# EEM_Connectors.net
KiCad netlist of a schematic drawn in Altium Designer
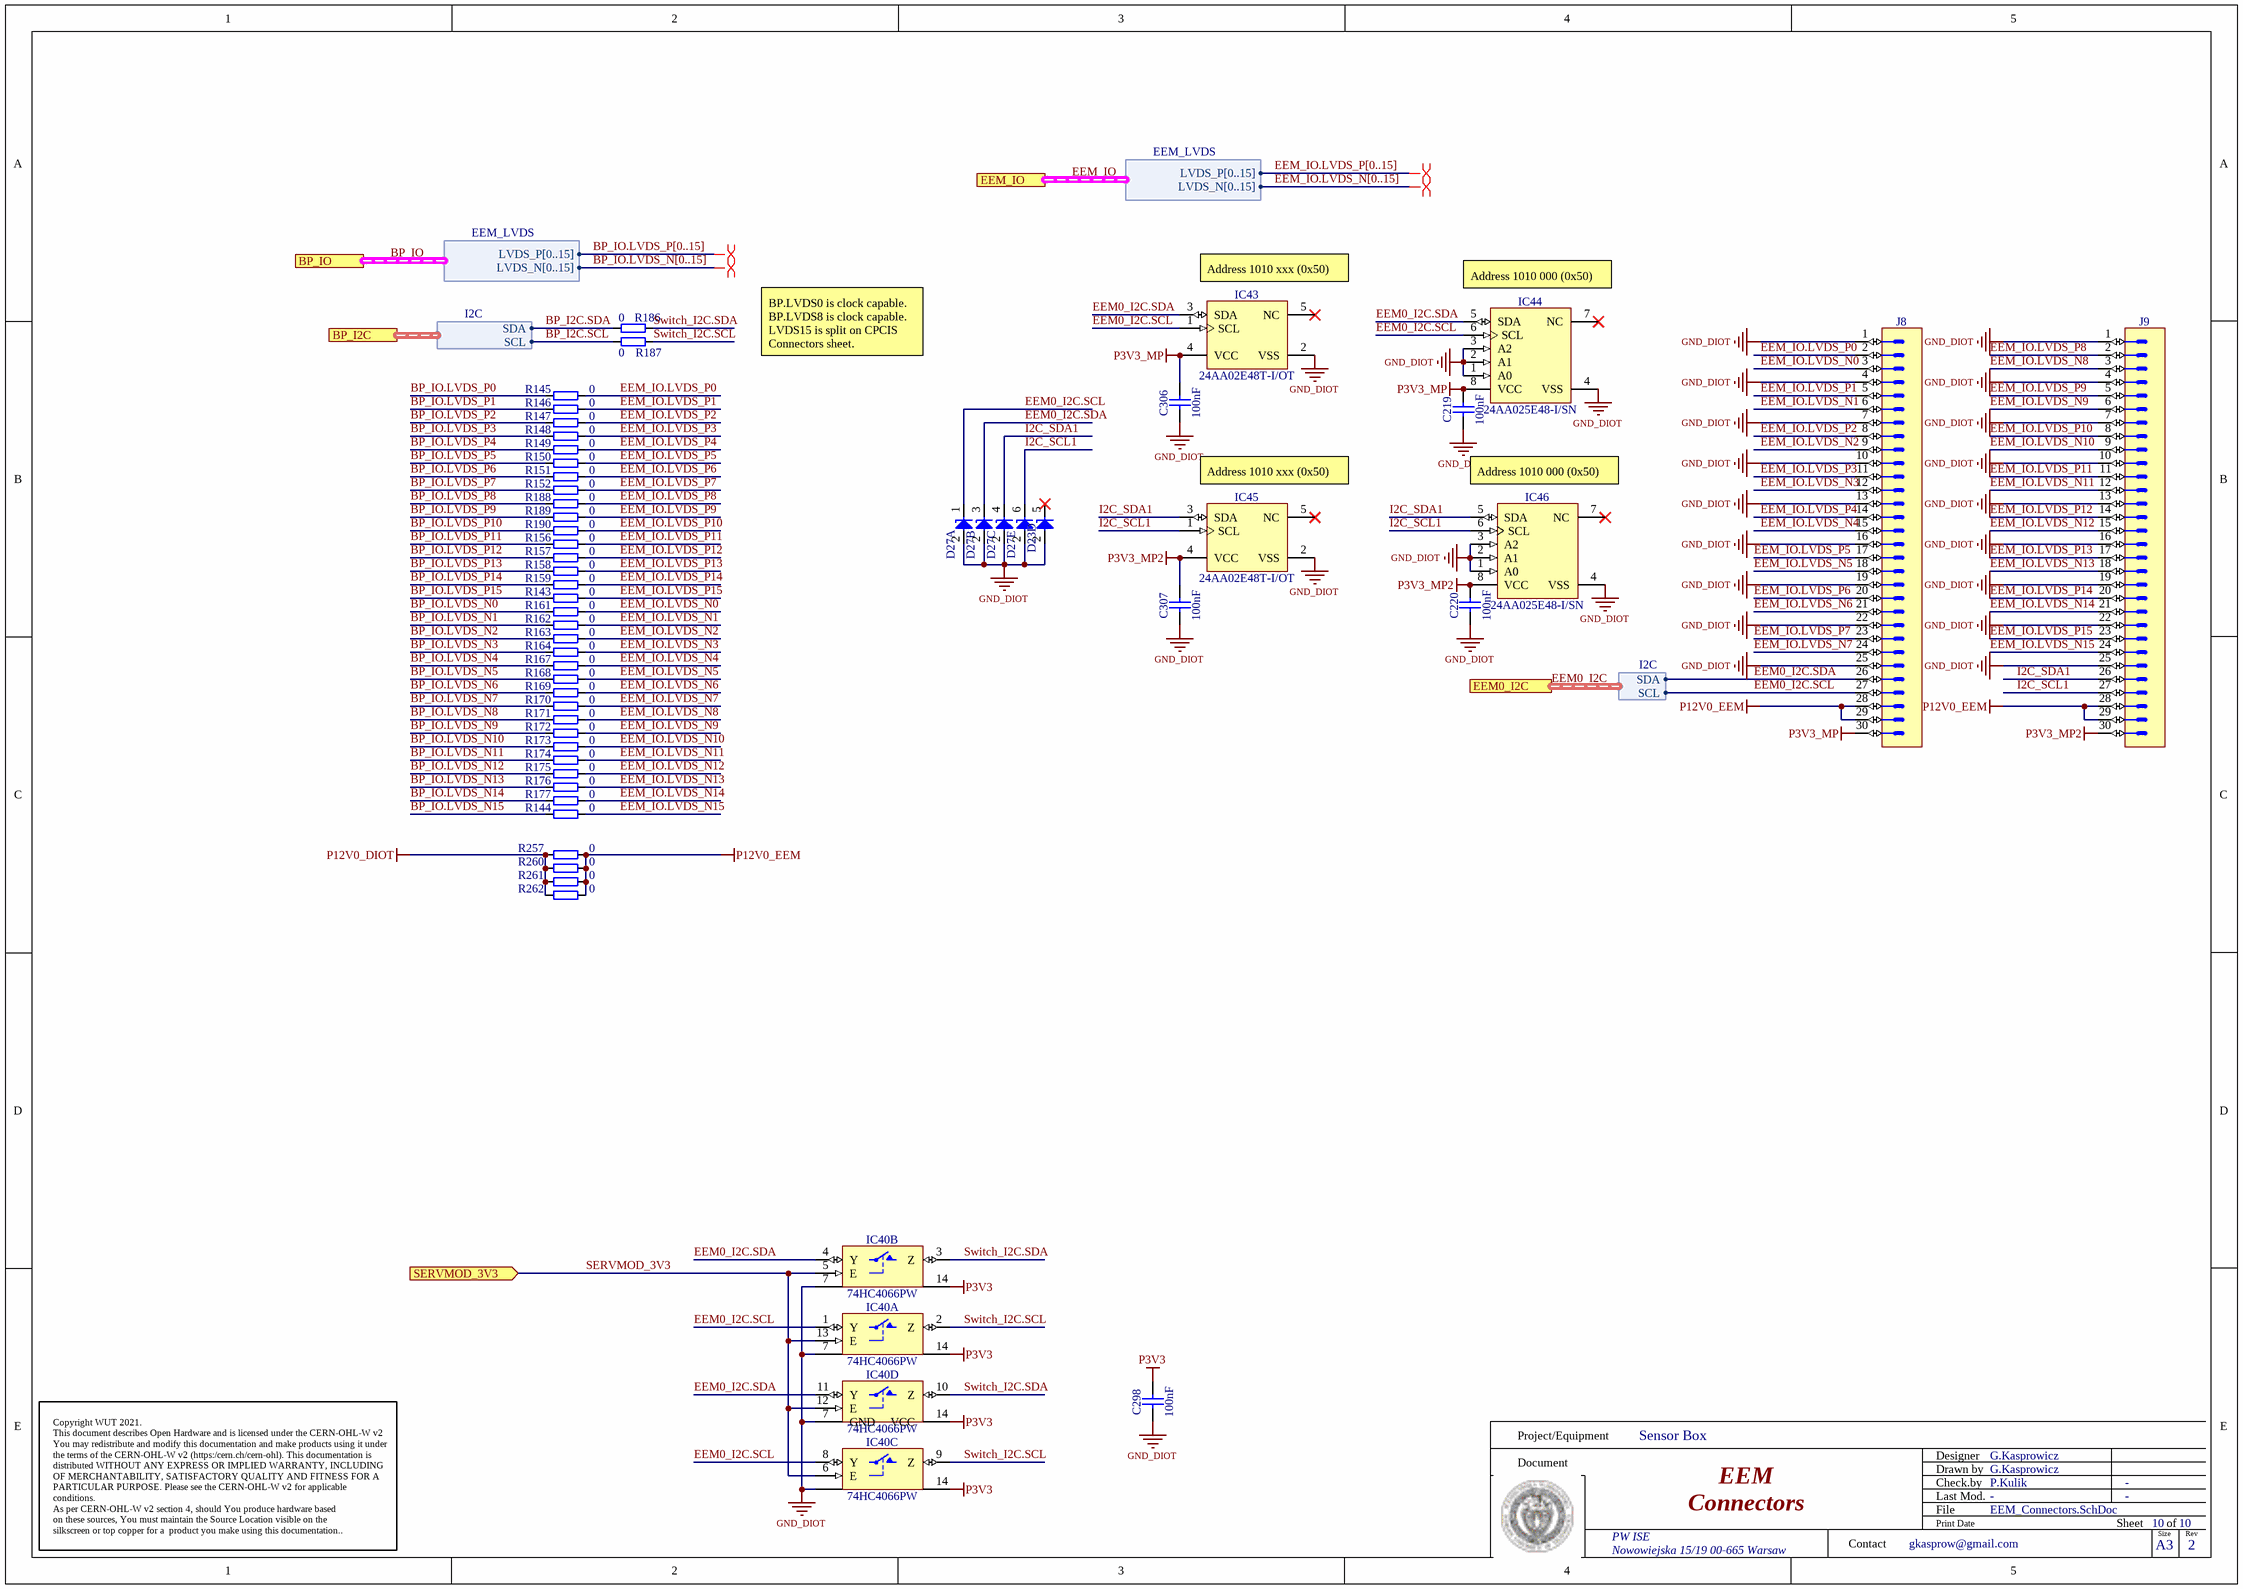
[diagram p0: EEM_Connectors.SchDoc]

(export (version "E")
  (design (tool "Eeschema 10.0.6"))
  (components
    (comp (ref "C219")
      (value "100nF")
      (footprint "CAPC1005X55N")
      (description "Non-polarised capacitor")
      (fields
        (field (name "PART NUMBER") "CC0402_100NF_50V_10%_X7R")
        (field (name "VOLTAGE") "50V")
        (field (name "AUTHOR") "CERN DEM MR")
      )
      (libsource (lib "Capacitors") (part "Capacitor - non polarized"))
    )
    (comp (ref "C220")
      (value "100nF")
      (footprint "CAPC1005X55N")
      (description "Non-polarised capacitor")
      (fields
        (field (name "PART NUMBER") "CC0402_100NF_50V_10%_X7R")
        (field (name "VOLTAGE") "50V")
        (field (name "AUTHOR") "CERN DEM MR")
      )
      (libsource (lib "Capacitors") (part "Capacitor - non polarized"))
    )
    (comp (ref "C298")
      (value "100nF")
      (footprint "CAPC1005X55N")
      (description "Non-polarised capacitor")
      (fields
        (field (name "PART NUMBER") "CC0402_100NF_50V_10%_X7R")
        (field (name "VOLTAGE") "50V")
        (field (name "AUTHOR") "CERN DEM MR")
      )
      (libsource (lib "Capacitors") (part "Capacitor - non polarized"))
    )
    (comp (ref "C306")
      (value "100nF")
      (footprint "CAPC1005X55N")
      (description "Non-polarised capacitor")
      (fields
        (field (name "PART NUMBER") "CC0402_100NF_50V_10%_X7R")
        (field (name "VOLTAGE") "50V")
        (field (name "AUTHOR") "CERN DEM MR")
      )
      (libsource (lib "Capacitors") (part "Capacitor - non polarized"))
    )
    (comp (ref "C307")
      (value "100nF")
      (footprint "CAPC1005X55N")
      (description "Non-polarised capacitor")
      (fields
        (field (name "PART NUMBER") "CC0402_100NF_50V_10%_X7R")
        (field (name "VOLTAGE") "50V")
        (field (name "AUTHOR") "CERN DEM MR")
      )
      (libsource (lib "Capacitors") (part "Capacitor - non polarized"))
    )
    (comp (ref "D23")
      (value "PESD3V3L5UY")
      (footprint "SOT65P210X110-6N")
      (description "Fivefold ESD Protection Diode Arrays")
      (fields
        (field (name "VOLTAGE") "3.3V")
        (field (name "POWER") "200W")
        (field (name "AUTHOR") "CERN DEM WB")
      )
      (libsource (lib "ICs And Semiconductors") (part "PESD Array 5diodes 6pins Common anode2"))
    )
    (comp (ref "D27")
      (value "PESD3V3L5UY")
      (footprint "SOT65P210X110-6N")
      (description "Fivefold ESD Protection Diode Arrays")
      (fields
        (field (name "VOLTAGE") "3.3V")
        (field (name "POWER") "200W")
        (field (name "AUTHOR") "CERN DEM WB")
      )
      (libsource (lib "ICs And Semiconductors") (part "PESD Array 5diodes 6pins Common anode2"))
    )
    (comp (ref "IC40")
      (value "74HC4066PW")
      (footprint "SOP65P640X110-14N")
      (fields (field (name "MANUFACTURER") "NXP SEMICONDUCTORS") (field (name "AUTHOR") "CERN DEM JLC"))
      (libsource (lib "ICs And Semiconductors") (part "4066"))
    )
    (comp (ref "IC43")
      (value "24AA02E48T-I/OT")
      (footprint "SOT95P280X145-5N")
      (description "1.7V-5.5V, 2K I2C Serial EEPROM With EUI-48 Node Identity")
      (fields (field (name "MANUFACTURER") "MICROCHIP TECHNOLOGY") (field (name "AUTHOR") "CERN DEM MR"))
      (libsource (lib "ICs And Semiconductors") (part "24AA02E48T-I/OT"))
    )
    (comp (ref "IC44")
      (value "24AA025E48-I/SN")
      (footprint "SOIC127P600X175-8N")
      (description "1.7V-5.5V, 2K I2C™ Serial EEPROMs with EUI-48™ Node Identity")
      (fields (field (name "MANUFACTURER") "MICROCHIP TECHNOLOGY") (field (name "AUTHOR") "CERN DEM MR"))
      (libsource (lib "ICs And Semiconductors") (part "24AA025E48-I/SN"))
    )
    (comp (ref "IC45")
      (value "24AA02E48T-I/OT")
      (footprint "SOT95P280X145-5N")
      (description "1.7V-5.5V, 2K I2C Serial EEPROM With EUI-48 Node Identity")
      (fields (field (name "MANUFACTURER") "MICROCHIP TECHNOLOGY") (field (name "AUTHOR") "CERN DEM MR"))
      (libsource (lib "ICs And Semiconductors") (part "24AA02E48T-I/OT"))
    )
    (comp (ref "IC46")
      (value "24AA025E48-I/SN")
      (footprint "SOIC127P600X175-8N")
      (description "1.7V-5.5V, 2K I2C™ Serial EEPROMs with EUI-48™ Node Identity")
      (fields (field (name "MANUFACTURER") "MICROCHIP TECHNOLOGY") (field (name "AUTHOR") "CERN DEM MR"))
      (libsource (lib "ICs And Semiconductors") (part "24AA025E48-I/SN"))
    )
    (comp (ref "J8")
      (value "~")
      (footprint "3M_N2530-6002RB")
      (description "Connector 30 Male")
      (fields
        (field (name "PART NUMBER") "3M_N2530-6002RB")
        (field (name "MANUFACTURER") "3M")
        (field (name "AUTHOR") "CERN DEM JLC")
      )
      (libsource (lib "Connectors") (part "Connector 30 Male"))
    )
    (comp (ref "J9")
      (value "~")
      (footprint "3M_N2530-6002RB")
      (description "Connector 30 Male")
      (fields
        (field (name "PART NUMBER") "3M_N2530-6002RB")
        (field (name "MANUFACTURER") "3M")
        (field (name "AUTHOR") "CERN DEM JLC")
      )
      (libsource (lib "Connectors") (part "Connector 30 Male"))
    )
    (comp (ref "R143")
      (value "0")
      (footprint "RESC1005X40N")
      (description "Resistor")
      (fields
        (field (name "PART NUMBER") "R0402_0R_JUMPER")
        (field (name "MANUFACTURER") "GENERIC")
        (field (name "AUTHOR") "CERN DEM JLC")
      )
      (libsource (lib "Resistors") (part "Resistor"))
    )
    (comp (ref "R144")
      (value "0")
      (footprint "RESC1005X40N")
      (description "Resistor")
      (fields
        (field (name "PART NUMBER") "R0402_0R_JUMPER")
        (field (name "MANUFACTURER") "GENERIC")
        (field (name "AUTHOR") "CERN DEM JLC")
      )
      (libsource (lib "Resistors") (part "Resistor"))
    )
    (comp (ref "R145")
      (value "0")
      (footprint "RESC1005X40N")
      (description "Resistor")
      (fields
        (field (name "PART NUMBER") "R0402_0R_JUMPER")
        (field (name "MANUFACTURER") "GENERIC")
        (field (name "AUTHOR") "CERN DEM JLC")
      )
      (libsource (lib "Resistors") (part "Resistor"))
    )
    (comp (ref "R146")
      (value "0")
      (footprint "RESC1005X40N")
      (description "Resistor")
      (fields
        (field (name "PART NUMBER") "R0402_0R_JUMPER")
        (field (name "MANUFACTURER") "GENERIC")
        (field (name "AUTHOR") "CERN DEM JLC")
      )
      (libsource (lib "Resistors") (part "Resistor"))
    )
    (comp (ref "R147")
      (value "0")
      (footprint "RESC1005X40N")
      (description "Resistor")
      (fields
        (field (name "PART NUMBER") "R0402_0R_JUMPER")
        (field (name "MANUFACTURER") "GENERIC")
        (field (name "AUTHOR") "CERN DEM JLC")
      )
      (libsource (lib "Resistors") (part "Resistor"))
    )
    (comp (ref "R148")
      (value "0")
      (footprint "RESC1005X40N")
      (description "Resistor")
      (fields
        (field (name "PART NUMBER") "R0402_0R_JUMPER")
        (field (name "MANUFACTURER") "GENERIC")
        (field (name "AUTHOR") "CERN DEM JLC")
      )
      (libsource (lib "Resistors") (part "Resistor"))
    )
    (comp (ref "R149")
      (value "0")
      (footprint "RESC1005X40N")
      (description "Resistor")
      (fields
        (field (name "PART NUMBER") "R0402_0R_JUMPER")
        (field (name "MANUFACTURER") "GENERIC")
        (field (name "AUTHOR") "CERN DEM JLC")
      )
      (libsource (lib "Resistors") (part "Resistor"))
    )
    (comp (ref "R150")
      (value "0")
      (footprint "RESC1005X40N")
      (description "Resistor")
      (fields
        (field (name "PART NUMBER") "R0402_0R_JUMPER")
        (field (name "MANUFACTURER") "GENERIC")
        (field (name "AUTHOR") "CERN DEM JLC")
      )
      (libsource (lib "Resistors") (part "Resistor"))
    )
    (comp (ref "R151")
      (value "0")
      (footprint "RESC1005X40N")
      (description "Resistor")
      (fields
        (field (name "PART NUMBER") "R0402_0R_JUMPER")
        (field (name "MANUFACTURER") "GENERIC")
        (field (name "AUTHOR") "CERN DEM JLC")
      )
      (libsource (lib "Resistors") (part "Resistor"))
    )
    (comp (ref "R152")
      (value "0")
      (footprint "RESC1005X40N")
      (description "Resistor")
      (fields
        (field (name "PART NUMBER") "R0402_0R_JUMPER")
        (field (name "MANUFACTURER") "GENERIC")
        (field (name "AUTHOR") "CERN DEM JLC")
      )
      (libsource (lib "Resistors") (part "Resistor"))
    )
    (comp (ref "R156")
      (value "0")
      (footprint "RESC1005X40N")
      (description "Resistor")
      (fields
        (field (name "PART NUMBER") "R0402_0R_JUMPER")
        (field (name "MANUFACTURER") "GENERIC")
        (field (name "AUTHOR") "CERN DEM JLC")
      )
      (libsource (lib "Resistors") (part "Resistor"))
    )
    (comp (ref "R157")
      (value "0")
      (footprint "RESC1005X40N")
      (description "Resistor")
      (fields
        (field (name "PART NUMBER") "R0402_0R_JUMPER")
        (field (name "MANUFACTURER") "GENERIC")
        (field (name "AUTHOR") "CERN DEM JLC")
      )
      (libsource (lib "Resistors") (part "Resistor"))
    )
    (comp (ref "R158")
      (value "0")
      (footprint "RESC1005X40N")
      (description "Resistor")
      (fields
        (field (name "PART NUMBER") "R0402_0R_JUMPER")
        (field (name "MANUFACTURER") "GENERIC")
        (field (name "AUTHOR") "CERN DEM JLC")
      )
      (libsource (lib "Resistors") (part "Resistor"))
    )
    (comp (ref "R159")
      (value "0")
      (footprint "RESC1005X40N")
      (description "Resistor")
      (fields
        (field (name "PART NUMBER") "R0402_0R_JUMPER")
        (field (name "MANUFACTURER") "GENERIC")
        (field (name "AUTHOR") "CERN DEM JLC")
      )
      (libsource (lib "Resistors") (part "Resistor"))
    )
    (comp (ref "R161")
      (value "0")
      (footprint "RESC1005X40N")
      (description "Resistor")
      (fields
        (field (name "PART NUMBER") "R0402_0R_JUMPER")
        (field (name "MANUFACTURER") "GENERIC")
        (field (name "AUTHOR") "CERN DEM JLC")
      )
      (libsource (lib "Resistors") (part "Resistor"))
    )
    (comp (ref "R162")
      (value "0")
      (footprint "RESC1005X40N")
      (description "Resistor")
      (fields
        (field (name "PART NUMBER") "R0402_0R_JUMPER")
        (field (name "MANUFACTURER") "GENERIC")
        (field (name "AUTHOR") "CERN DEM JLC")
      )
      (libsource (lib "Resistors") (part "Resistor"))
    )
    (comp (ref "R163")
      (value "0")
      (footprint "RESC1005X40N")
      (description "Resistor")
      (fields
        (field (name "PART NUMBER") "R0402_0R_JUMPER")
        (field (name "MANUFACTURER") "GENERIC")
        (field (name "AUTHOR") "CERN DEM JLC")
      )
      (libsource (lib "Resistors") (part "Resistor"))
    )
    (comp (ref "R164")
      (value "0")
      (footprint "RESC1005X40N")
      (description "Resistor")
      (fields
        (field (name "PART NUMBER") "R0402_0R_JUMPER")
        (field (name "MANUFACTURER") "GENERIC")
        (field (name "AUTHOR") "CERN DEM JLC")
      )
      (libsource (lib "Resistors") (part "Resistor"))
    )
    (comp (ref "R167")
      (value "0")
      (footprint "RESC1005X40N")
      (description "Resistor")
      (fields
        (field (name "PART NUMBER") "R0402_0R_JUMPER")
        (field (name "MANUFACTURER") "GENERIC")
        (field (name "AUTHOR") "CERN DEM JLC")
      )
      (libsource (lib "Resistors") (part "Resistor"))
    )
    (comp (ref "R168")
      (value "0")
      (footprint "RESC1005X40N")
      (description "Resistor")
      (fields
        (field (name "PART NUMBER") "R0402_0R_JUMPER")
        (field (name "MANUFACTURER") "GENERIC")
        (field (name "AUTHOR") "CERN DEM JLC")
      )
      (libsource (lib "Resistors") (part "Resistor"))
    )
    (comp (ref "R169")
      (value "0")
      (footprint "RESC1005X40N")
      (description "Resistor")
      (fields
        (field (name "PART NUMBER") "R0402_0R_JUMPER")
        (field (name "MANUFACTURER") "GENERIC")
        (field (name "AUTHOR") "CERN DEM JLC")
      )
      (libsource (lib "Resistors") (part "Resistor"))
    )
    (comp (ref "R170")
      (value "0")
      (footprint "RESC1005X40N")
      (description "Resistor")
      (fields
        (field (name "PART NUMBER") "R0402_0R_JUMPER")
        (field (name "MANUFACTURER") "GENERIC")
        (field (name "AUTHOR") "CERN DEM JLC")
      )
      (libsource (lib "Resistors") (part "Resistor"))
    )
    (comp (ref "R171")
      (value "0")
      (footprint "RESC1005X40N")
      (description "Resistor")
      (fields
        (field (name "PART NUMBER") "R0402_0R_JUMPER")
        (field (name "MANUFACTURER") "GENERIC")
        (field (name "AUTHOR") "CERN DEM JLC")
      )
      (libsource (lib "Resistors") (part "Resistor"))
    )
    (comp (ref "R172")
      (value "0")
      (footprint "RESC1005X40N")
      (description "Resistor")
      (fields
        (field (name "PART NUMBER") "R0402_0R_JUMPER")
        (field (name "MANUFACTURER") "GENERIC")
        (field (name "AUTHOR") "CERN DEM JLC")
      )
      (libsource (lib "Resistors") (part "Resistor"))
    )
    (comp (ref "R173")
      (value "0")
      (footprint "RESC1005X40N")
      (description "Resistor")
      (fields
        (field (name "PART NUMBER") "R0402_0R_JUMPER")
        (field (name "MANUFACTURER") "GENERIC")
        (field (name "AUTHOR") "CERN DEM JLC")
      )
      (libsource (lib "Resistors") (part "Resistor"))
    )
    (comp (ref "R174")
      (value "0")
      (footprint "RESC1005X40N")
      (description "Resistor")
      (fields
        (field (name "PART NUMBER") "R0402_0R_JUMPER")
        (field (name "MANUFACTURER") "GENERIC")
        (field (name "AUTHOR") "CERN DEM JLC")
      )
      (libsource (lib "Resistors") (part "Resistor"))
    )
    (comp (ref "R175")
      (value "0")
      (footprint "RESC1005X40N")
      (description "Resistor")
      (fields
        (field (name "PART NUMBER") "R0402_0R_JUMPER")
        (field (name "MANUFACTURER") "GENERIC")
        (field (name "AUTHOR") "CERN DEM JLC")
      )
      (libsource (lib "Resistors") (part "Resistor"))
    )
    (comp (ref "R176")
      (value "0")
      (footprint "RESC1005X40N")
      (description "Resistor")
      (fields
        (field (name "PART NUMBER") "R0402_0R_JUMPER")
        (field (name "MANUFACTURER") "GENERIC")
        (field (name "AUTHOR") "CERN DEM JLC")
      )
      (libsource (lib "Resistors") (part "Resistor"))
    )
    (comp (ref "R177")
      (value "0")
      (footprint "RESC1005X40N")
      (description "Resistor")
      (fields
        (field (name "PART NUMBER") "R0402_0R_JUMPER")
        (field (name "MANUFACTURER") "GENERIC")
        (field (name "AUTHOR") "CERN DEM JLC")
      )
      (libsource (lib "Resistors") (part "Resistor"))
    )
    (comp (ref "R186")
      (value "0")
      (footprint "RESC1005X40N")
      (description "Resistor")
      (fields
        (field (name "PART NUMBER") "R0402_0R_JUMPER")
        (field (name "MANUFACTURER") "GENERIC")
        (field (name "AUTHOR") "CERN DEM JLC")
      )
      (libsource (lib "Resistors") (part "Resistor"))
    )
    (comp (ref "R187")
      (value "0")
      (footprint "RESC1005X40N")
      (description "Resistor")
      (fields
        (field (name "PART NUMBER") "R0402_0R_JUMPER")
        (field (name "MANUFACTURER") "GENERIC")
        (field (name "AUTHOR") "CERN DEM JLC")
      )
      (libsource (lib "Resistors") (part "Resistor"))
    )
    (comp (ref "R188")
      (value "0")
      (footprint "RESC1005X40N")
      (description "Resistor")
      (fields
        (field (name "PART NUMBER") "R0402_0R_JUMPER")
        (field (name "MANUFACTURER") "GENERIC")
        (field (name "AUTHOR") "CERN DEM JLC")
      )
      (libsource (lib "Resistors") (part "Resistor"))
    )
    (comp (ref "R189")
      (value "0")
      (footprint "RESC1005X40N")
      (description "Resistor")
      (fields
        (field (name "PART NUMBER") "R0402_0R_JUMPER")
        (field (name "MANUFACTURER") "GENERIC")
        (field (name "AUTHOR") "CERN DEM JLC")
      )
      (libsource (lib "Resistors") (part "Resistor"))
    )
    (comp (ref "R190")
      (value "0")
      (footprint "RESC1005X40N")
      (description "Resistor")
      (fields
        (field (name "PART NUMBER") "R0402_0R_JUMPER")
        (field (name "MANUFACTURER") "GENERIC")
        (field (name "AUTHOR") "CERN DEM JLC")
      )
      (libsource (lib "Resistors") (part "Resistor"))
    )
    (comp (ref "R257")
      (value "0")
      (footprint "RESC1005X40N")
      (description "Resistor")
      (fields
        (field (name "PART NUMBER") "R0402_0R_JUMPER")
        (field (name "MANUFACTURER") "GENERIC")
        (field (name "AUTHOR") "CERN DEM JLC")
      )
      (libsource (lib "Resistors") (part "Resistor"))
    )
    (comp (ref "R260")
      (value "0")
      (footprint "RESC1005X40N")
      (description "Resistor")
      (fields
        (field (name "PART NUMBER") "R0402_0R_JUMPER")
        (field (name "MANUFACTURER") "GENERIC")
        (field (name "AUTHOR") "CERN DEM JLC")
      )
      (libsource (lib "Resistors") (part "Resistor"))
    )
    (comp (ref "R261")
      (value "0")
      (footprint "RESC1005X40N")
      (description "Resistor")
      (fields
        (field (name "PART NUMBER") "R0402_0R_JUMPER")
        (field (name "MANUFACTURER") "GENERIC")
        (field (name "AUTHOR") "CERN DEM JLC")
      )
      (libsource (lib "Resistors") (part "Resistor"))
    )
    (comp (ref "R262")
      (value "0")
      (footprint "RESC1005X40N")
      (description "Resistor")
      (fields
        (field (name "PART NUMBER") "R0402_0R_JUMPER")
        (field (name "MANUFACTURER") "GENERIC")
        (field (name "AUTHOR") "CERN DEM JLC")
      )
      (libsource (lib "Resistors") (part "Resistor"))
    )
  )
  (nets
    (net (code "5") (name "/BP_I2C.SCL") (class "Default")
      (node (ref "R187") (pin "1") (pinfunction "1_1") (pintype "passive"))
    )
    (net (code "6") (name "/BP_I2C.SDA") (class "Default")
      (node (ref "R186") (pin "1") (pinfunction "1_1") (pintype "passive"))
    )
    (net (code "7") (name "/BP_IO.LVDS_N0") (class "Default")
      (node (ref "R161") (pin "1") (pinfunction "1_1") (pintype "passive"))
    )
    (net (code "8") (name "/BP_IO.LVDS_N1") (class "Default")
      (node (ref "R162") (pin "1") (pinfunction "1_1") (pintype "passive"))
    )
    (net (code "9") (name "/BP_IO.LVDS_N2") (class "Default")
      (node (ref "R163") (pin "1") (pinfunction "1_1") (pintype "passive"))
    )
    (net (code "10") (name "/BP_IO.LVDS_N3") (class "Default")
      (node (ref "R164") (pin "1") (pinfunction "1_1") (pintype "passive"))
    )
    (net (code "11") (name "/BP_IO.LVDS_N4") (class "Default")
      (node (ref "R167") (pin "1") (pinfunction "1_1") (pintype "passive"))
    )
    (net (code "12") (name "/BP_IO.LVDS_N5") (class "Default")
      (node (ref "R168") (pin "1") (pinfunction "1_1") (pintype "passive"))
    )
    (net (code "13") (name "/BP_IO.LVDS_N6") (class "Default")
      (node (ref "R169") (pin "1") (pinfunction "1_1") (pintype "passive"))
    )
    (net (code "14") (name "/BP_IO.LVDS_N7") (class "Default")
      (node (ref "R170") (pin "1") (pinfunction "1_1") (pintype "passive"))
    )
    (net (code "15") (name "/BP_IO.LVDS_N8") (class "Default")
      (node (ref "R171") (pin "1") (pinfunction "1_1") (pintype "passive"))
    )
    (net (code "16") (name "/BP_IO.LVDS_N9") (class "Default")
      (node (ref "R172") (pin "1") (pinfunction "1_1") (pintype "passive"))
    )
    (net (code "17") (name "/BP_IO.LVDS_N10") (class "Default")
      (node (ref "R173") (pin "1") (pinfunction "1_1") (pintype "passive"))
    )
    (net (code "18") (name "/BP_IO.LVDS_N11") (class "Default")
      (node (ref "R174") (pin "1") (pinfunction "1_1") (pintype "passive"))
    )
    (net (code "19") (name "/BP_IO.LVDS_N12") (class "Default")
      (node (ref "R175") (pin "1") (pinfunction "1_1") (pintype "passive"))
    )
    (net (code "20") (name "/BP_IO.LVDS_N13") (class "Default")
      (node (ref "R176") (pin "1") (pinfunction "1_1") (pintype "passive"))
    )
    (net (code "21") (name "/BP_IO.LVDS_N14") (class "Default")
      (node (ref "R177") (pin "1") (pinfunction "1_1") (pintype "passive"))
    )
    (net (code "22") (name "/BP_IO.LVDS_N15") (class "Default")
      (node (ref "R144") (pin "2") (pinfunction "2_2") (pintype "passive"))
    )
    (net (code "24") (name "/BP_IO.LVDS_P0") (class "Default")
      (node (ref "R145") (pin "1") (pinfunction "1_1") (pintype "passive"))
    )
    (net (code "25") (name "/BP_IO.LVDS_P1") (class "Default")
      (node (ref "R146") (pin "1") (pinfunction "1_1") (pintype "passive"))
    )
    (net (code "26") (name "/BP_IO.LVDS_P2") (class "Default")
      (node (ref "R147") (pin "1") (pinfunction "1_1") (pintype "passive"))
    )
    (net (code "27") (name "/BP_IO.LVDS_P3") (class "Default")
      (node (ref "R148") (pin "1") (pinfunction "1_1") (pintype "passive"))
    )
    (net (code "28") (name "/BP_IO.LVDS_P4") (class "Default")
      (node (ref "R149") (pin "1") (pinfunction "1_1") (pintype "passive"))
    )
    (net (code "29") (name "/BP_IO.LVDS_P5") (class "Default")
      (node (ref "R150") (pin "1") (pinfunction "1_1") (pintype "passive"))
    )
    (net (code "30") (name "/BP_IO.LVDS_P6") (class "Default")
      (node (ref "R151") (pin "1") (pinfunction "1_1") (pintype "passive"))
    )
    (net (code "31") (name "/BP_IO.LVDS_P7") (class "Default")
      (node (ref "R152") (pin "1") (pinfunction "1_1") (pintype "passive"))
    )
    (net (code "32") (name "/BP_IO.LVDS_P8") (class "Default")
      (node (ref "R188") (pin "1") (pinfunction "1_1") (pintype "passive"))
    )
    (net (code "33") (name "/BP_IO.LVDS_P9") (class "Default")
      (node (ref "R189") (pin "1") (pinfunction "1_1") (pintype "passive"))
    )
    (net (code "34") (name "/BP_IO.LVDS_P10") (class "Default")
      (node (ref "R190") (pin "1") (pinfunction "1_1") (pintype "passive"))
    )
    (net (code "35") (name "/BP_IO.LVDS_P11") (class "Default")
      (node (ref "R156") (pin "1") (pinfunction "1_1") (pintype "passive"))
    )
    (net (code "36") (name "/BP_IO.LVDS_P12") (class "Default")
      (node (ref "R157") (pin "1") (pinfunction "1_1") (pintype "passive"))
    )
    (net (code "37") (name "/BP_IO.LVDS_P13") (class "Default")
      (node (ref "R158") (pin "1") (pinfunction "1_1") (pintype "passive"))
    )
    (net (code "38") (name "/BP_IO.LVDS_P14") (class "Default")
      (node (ref "R159") (pin "1") (pinfunction "1_1") (pintype "passive"))
    )
    (net (code "39") (name "/BP_IO.LVDS_P15") (class "Default")
      (node (ref "R143") (pin "2") (pinfunction "2_2") (pintype "passive"))
    )
    (net (code "42") (name "/EEM0_I2C.SCL") (class "Default")
      (node (ref "D27") (pin "1") (pinfunction "C_1") (pintype "passive"))
      (node (ref "IC40") (pin "1") (pinfunction "Y_1") (pintype "bidirectional"))
      (node (ref "IC40") (pin "8") (pinfunction "Y_8") (pintype "bidirectional"))
      (node (ref "IC43") (pin "1") (pinfunction "SCL_1") (pintype "input"))
      (node (ref "IC44") (pin "6") (pinfunction "SCL_6") (pintype "input"))
      (node (ref "J8") (pin "27") (pinfunction "27_27") (pintype "bidirectional"))
    )
    (net (code "43") (name "/EEM0_I2C.SDA") (class "Default")
      (node (ref "D27") (pin "3") (pinfunction "C_3") (pintype "passive"))
      (node (ref "IC40") (pin "11") (pinfunction "Y_11") (pintype "bidirectional"))
      (node (ref "IC40") (pin "4") (pinfunction "Y_4") (pintype "bidirectional"))
      (node (ref "IC43") (pin "3") (pinfunction "SDA_3") (pintype "bidirectional"))
      (node (ref "IC44") (pin "5") (pinfunction "SDA_5") (pintype "bidirectional"))
      (node (ref "J8") (pin "26") (pinfunction "26_26") (pintype "bidirectional"))
    )
    (net (code "45") (name "/EEM_IO.LVDS_N0") (class "Default")
      (node (ref "J8") (pin "3") (pinfunction "3_3") (pintype "bidirectional"))
      (node (ref "R161") (pin "2") (pinfunction "2_2") (pintype "passive"))
    )
    (net (code "46") (name "/EEM_IO.LVDS_N1") (class "Default")
      (node (ref "J8") (pin "6") (pinfunction "6_6") (pintype "bidirectional"))
      (node (ref "R162") (pin "2") (pinfunction "2_2") (pintype "passive"))
    )
    (net (code "47") (name "/EEM_IO.LVDS_N2") (class "Default")
      (node (ref "J8") (pin "9") (pinfunction "9_9") (pintype "bidirectional"))
      (node (ref "R163") (pin "2") (pinfunction "2_2") (pintype "passive"))
    )
    (net (code "48") (name "/EEM_IO.LVDS_N3") (class "Default")
      (node (ref "J8") (pin "12") (pinfunction "12_12") (pintype "bidirectional"))
      (node (ref "R164") (pin "2") (pinfunction "2_2") (pintype "passive"))
    )
    (net (code "49") (name "/EEM_IO.LVDS_N4") (class "Default")
      (node (ref "J8") (pin "15") (pinfunction "15_15") (pintype "bidirectional"))
      (node (ref "R167") (pin "2") (pinfunction "2_2") (pintype "passive"))
    )
    (net (code "50") (name "/EEM_IO.LVDS_N5") (class "Default")
      (node (ref "J8") (pin "18") (pinfunction "18_18") (pintype "bidirectional"))
      (node (ref "R168") (pin "2") (pinfunction "2_2") (pintype "passive"))
    )
    (net (code "51") (name "/EEM_IO.LVDS_N6") (class "Default")
      (node (ref "J8") (pin "21") (pinfunction "21_21") (pintype "bidirectional"))
      (node (ref "R169") (pin "2") (pinfunction "2_2") (pintype "passive"))
    )
    (net (code "52") (name "/EEM_IO.LVDS_N7") (class "Default")
      (node (ref "J8") (pin "24") (pinfunction "24_24") (pintype "bidirectional"))
      (node (ref "R170") (pin "2") (pinfunction "2_2") (pintype "passive"))
    )
    (net (code "53") (name "/EEM_IO.LVDS_N8") (class "Default")
      (node (ref "J9") (pin "3") (pinfunction "3_3") (pintype "bidirectional"))
      (node (ref "R171") (pin "2") (pinfunction "2_2") (pintype "passive"))
    )
    (net (code "54") (name "/EEM_IO.LVDS_N9") (class "Default")
      (node (ref "J9") (pin "6") (pinfunction "6_6") (pintype "bidirectional"))
      (node (ref "R172") (pin "2") (pinfunction "2_2") (pintype "passive"))
    )
    (net (code "55") (name "/EEM_IO.LVDS_N10") (class "Default")
      (node (ref "J9") (pin "9") (pinfunction "9_9") (pintype "bidirectional"))
      (node (ref "R173") (pin "2") (pinfunction "2_2") (pintype "passive"))
    )
    (net (code "56") (name "/EEM_IO.LVDS_N11") (class "Default")
      (node (ref "J9") (pin "12") (pinfunction "12_12") (pintype "bidirectional"))
      (node (ref "R174") (pin "2") (pinfunction "2_2") (pintype "passive"))
    )
    (net (code "57") (name "/EEM_IO.LVDS_N12") (class "Default")
      (node (ref "J9") (pin "15") (pinfunction "15_15") (pintype "bidirectional"))
      (node (ref "R175") (pin "2") (pinfunction "2_2") (pintype "passive"))
    )
    (net (code "58") (name "/EEM_IO.LVDS_N13") (class "Default")
      (node (ref "J9") (pin "18") (pinfunction "18_18") (pintype "bidirectional"))
      (node (ref "R176") (pin "2") (pinfunction "2_2") (pintype "passive"))
    )
    (net (code "59") (name "/EEM_IO.LVDS_N14") (class "Default")
      (node (ref "J9") (pin "21") (pinfunction "21_21") (pintype "bidirectional"))
      (node (ref "R177") (pin "2") (pinfunction "2_2") (pintype "passive"))
    )
    (net (code "60") (name "/EEM_IO.LVDS_N15") (class "Default")
      (node (ref "J9") (pin "24") (pinfunction "24_24") (pintype "bidirectional"))
      (node (ref "R144") (pin "1") (pinfunction "1_1") (pintype "passive"))
    )
    (net (code "62") (name "/EEM_IO.LVDS_P0") (class "Default")
      (node (ref "J8") (pin "2") (pinfunction "2_2") (pintype "bidirectional"))
      (node (ref "R145") (pin "2") (pinfunction "2_2") (pintype "passive"))
    )
    (net (code "63") (name "/EEM_IO.LVDS_P1") (class "Default")
      (node (ref "J8") (pin "5") (pinfunction "5_5") (pintype "bidirectional"))
      (node (ref "R146") (pin "2") (pinfunction "2_2") (pintype "passive"))
    )
    (net (code "64") (name "/EEM_IO.LVDS_P2") (class "Default")
      (node (ref "J8") (pin "8") (pinfunction "8_8") (pintype "bidirectional"))
      (node (ref "R147") (pin "2") (pinfunction "2_2") (pintype "passive"))
    )
    (net (code "65") (name "/EEM_IO.LVDS_P3") (class "Default")
      (node (ref "J8") (pin "11") (pinfunction "11_11") (pintype "bidirectional"))
      (node (ref "R148") (pin "2") (pinfunction "2_2") (pintype "passive"))
    )
    (net (code "66") (name "/EEM_IO.LVDS_P4") (class "Default")
      (node (ref "J8") (pin "14") (pinfunction "14_14") (pintype "bidirectional"))
      (node (ref "R149") (pin "2") (pinfunction "2_2") (pintype "passive"))
    )
    (net (code "67") (name "/EEM_IO.LVDS_P5") (class "Default")
      (node (ref "J8") (pin "17") (pinfunction "17_17") (pintype "bidirectional"))
      (node (ref "R150") (pin "2") (pinfunction "2_2") (pintype "passive"))
    )
    (net (code "68") (name "/EEM_IO.LVDS_P6") (class "Default")
      (node (ref "J8") (pin "20") (pinfunction "20_20") (pintype "bidirectional"))
      (node (ref "R151") (pin "2") (pinfunction "2_2") (pintype "passive"))
    )
    (net (code "69") (name "/EEM_IO.LVDS_P7") (class "Default")
      (node (ref "J8") (pin "23") (pinfunction "23_23") (pintype "bidirectional"))
      (node (ref "R152") (pin "2") (pinfunction "2_2") (pintype "passive"))
    )
    (net (code "70") (name "/EEM_IO.LVDS_P8") (class "Default")
      (node (ref "J9") (pin "2") (pinfunction "2_2") (pintype "bidirectional"))
      (node (ref "R188") (pin "2") (pinfunction "2_2") (pintype "passive"))
    )
    (net (code "71") (name "/EEM_IO.LVDS_P9") (class "Default")
      (node (ref "J9") (pin "5") (pinfunction "5_5") (pintype "bidirectional"))
      (node (ref "R189") (pin "2") (pinfunction "2_2") (pintype "passive"))
    )
    (net (code "72") (name "/EEM_IO.LVDS_P10") (class "Default")
      (node (ref "J9") (pin "8") (pinfunction "8_8") (pintype "bidirectional"))
      (node (ref "R190") (pin "2") (pinfunction "2_2") (pintype "passive"))
    )
    (net (code "73") (name "/EEM_IO.LVDS_P11") (class "Default")
      (node (ref "J9") (pin "11") (pinfunction "11_11") (pintype "bidirectional"))
      (node (ref "R156") (pin "2") (pinfunction "2_2") (pintype "passive"))
    )
    (net (code "74") (name "/EEM_IO.LVDS_P12") (class "Default")
      (node (ref "J9") (pin "14") (pinfunction "14_14") (pintype "bidirectional"))
      (node (ref "R157") (pin "2") (pinfunction "2_2") (pintype "passive"))
    )
    (net (code "75") (name "/EEM_IO.LVDS_P13") (class "Default")
      (node (ref "J9") (pin "17") (pinfunction "17_17") (pintype "bidirectional"))
      (node (ref "R158") (pin "2") (pinfunction "2_2") (pintype "passive"))
    )
    (net (code "76") (name "/EEM_IO.LVDS_P14") (class "Default")
      (node (ref "J9") (pin "20") (pinfunction "20_20") (pintype "bidirectional"))
      (node (ref "R159") (pin "2") (pinfunction "2_2") (pintype "passive"))
    )
    (net (code "77") (name "/EEM_IO.LVDS_P15") (class "Default")
      (node (ref "J9") (pin "23") (pinfunction "23_23") (pintype "bidirectional"))
      (node (ref "R143") (pin "1") (pinfunction "1_1") (pintype "passive"))
    )
    (net (code "78") (name "/I2C_SCL1") (class "Default")
      (node (ref "D27") (pin "6") (pinfunction "C_6") (pintype "passive"))
      (node (ref "IC45") (pin "1") (pinfunction "SCL_1") (pintype "input"))
      (node (ref "IC46") (pin "6") (pinfunction "SCL_6") (pintype "input"))
      (node (ref "J9") (pin "27") (pinfunction "27_27") (pintype "bidirectional"))
    )
    (net (code "79") (name "/I2C_SDA1") (class "Default")
      (node (ref "D27") (pin "4") (pinfunction "C_4") (pintype "passive"))
      (node (ref "IC45") (pin "3") (pinfunction "SDA_3") (pintype "bidirectional"))
      (node (ref "IC46") (pin "5") (pinfunction "SDA_5") (pintype "bidirectional"))
      (node (ref "J9") (pin "26") (pinfunction "26_26") (pintype "bidirectional"))
    )
    (net (code "80") (name "/SERVMOD_3V3") (class "Default")
      (node (ref "IC40") (pin "12") (pinfunction "E_12") (pintype "input"))
      (node (ref "IC40") (pin "13") (pinfunction "E_13") (pintype "input"))
      (node (ref "IC40") (pin "5") (pinfunction "E_5") (pintype "input"))
      (node (ref "IC40") (pin "6") (pinfunction "E_6") (pintype "input"))
    )
    (net (code "81") (name "/Switch_I2C.SCL") (class "Default")
      (node (ref "IC40") (pin "2") (pinfunction "Z_2") (pintype "bidirectional"))
      (node (ref "IC40") (pin "9") (pinfunction "Z_9") (pintype "bidirectional"))
      (node (ref "R187") (pin "2") (pinfunction "2_2") (pintype "passive"))
    )
    (net (code "82") (name "/Switch_I2C.SDA") (class "Default")
      (node (ref "IC40") (pin "10") (pinfunction "Z_10") (pintype "bidirectional"))
      (node (ref "IC40") (pin "3") (pinfunction "Z_3") (pintype "bidirectional"))
      (node (ref "R186") (pin "2") (pinfunction "2_2") (pintype "passive"))
    )
    (net (code "86") (name "GND_DIOT") (class "Default")
      (node (ref "C219") (pin "1") (pinfunction "1_1") (pintype "passive"))
      (node (ref "C220") (pin "1") (pinfunction "1_1") (pintype "passive"))
      (node (ref "C298") (pin "1") (pinfunction "1_1") (pintype "passive"))
      (node (ref "C306") (pin "1") (pinfunction "1_1") (pintype "passive"))
      (node (ref "C307") (pin "1") (pinfunction "1_1") (pintype "passive"))
      (node (ref "D23") (pin "2") (pinfunction "A_2") (pintype "passive"))
      (node (ref "D27") (pin "2") (pinfunction "A_2") (pintype "passive"))
      (node (ref "IC40") (pin "7") (pinfunction "GND_7") (pintype "power_in"))
      (node (ref "IC43") (pin "2") (pinfunction "VSS_2") (pintype "power_in"))
      (node (ref "IC44") (pin "1") (pinfunction "A0_1") (pintype "input"))
      (node (ref "IC44") (pin "2") (pinfunction "A1_2") (pintype "input"))
      (node (ref "IC44") (pin "3") (pinfunction "A2_3") (pintype "input"))
      (node (ref "IC44") (pin "4") (pinfunction "VSS_4") (pintype "power_in"))
      (node (ref "IC45") (pin "2") (pinfunction "VSS_2") (pintype "power_in"))
      (node (ref "IC46") (pin "1") (pinfunction "A0_1") (pintype "input"))
      (node (ref "IC46") (pin "2") (pinfunction "A1_2") (pintype "input"))
      (node (ref "IC46") (pin "3") (pinfunction "A2_3") (pintype "input"))
      (node (ref "IC46") (pin "4") (pinfunction "VSS_4") (pintype "power_in"))
      (node (ref "J8") (pin "1") (pinfunction "1_1") (pintype "bidirectional"))
      (node (ref "J8") (pin "10") (pinfunction "10_10") (pintype "bidirectional"))
      (node (ref "J8") (pin "13") (pinfunction "13_13") (pintype "bidirectional"))
      (node (ref "J8") (pin "16") (pinfunction "16_16") (pintype "bidirectional"))
      (node (ref "J8") (pin "19") (pinfunction "19_19") (pintype "bidirectional"))
      (node (ref "J8") (pin "22") (pinfunction "22_22") (pintype "bidirectional"))
      (node (ref "J8") (pin "25") (pinfunction "25_25") (pintype "bidirectional"))
      (node (ref "J8") (pin "4") (pinfunction "4_4") (pintype "bidirectional"))
      (node (ref "J8") (pin "7") (pinfunction "7_7") (pintype "bidirectional"))
      (node (ref "J9") (pin "1") (pinfunction "1_1") (pintype "bidirectional"))
      (node (ref "J9") (pin "10") (pinfunction "10_10") (pintype "bidirectional"))
      (node (ref "J9") (pin "13") (pinfunction "13_13") (pintype "bidirectional"))
      (node (ref "J9") (pin "16") (pinfunction "16_16") (pintype "bidirectional"))
      (node (ref "J9") (pin "19") (pinfunction "19_19") (pintype "bidirectional"))
      (node (ref "J9") (pin "22") (pinfunction "22_22") (pintype "bidirectional"))
      (node (ref "J9") (pin "25") (pinfunction "25_25") (pintype "bidirectional"))
      (node (ref "J9") (pin "4") (pinfunction "4_4") (pintype "bidirectional"))
      (node (ref "J9") (pin "7") (pinfunction "7_7") (pintype "bidirectional"))
    )
    (net (code "87") (name "P3V3") (class "Default")
      (node (ref "C298") (pin "2") (pinfunction "2_2") (pintype "passive"))
      (node (ref "IC40") (pin "14") (pinfunction "VCC_14") (pintype "power_in"))
    )
    (net (code "88") (name "P3V3_MP") (class "Default")
      (node (ref "C219") (pin "2") (pinfunction "2_2") (pintype "passive"))
      (node (ref "C306") (pin "2") (pinfunction "2_2") (pintype "passive"))
      (node (ref "IC43") (pin "4") (pinfunction "VCC_4") (pintype "power_in"))
      (node (ref "IC44") (pin "8") (pinfunction "VCC_8") (pintype "power_in"))
      (node (ref "J8") (pin "30") (pinfunction "30_30") (pintype "bidirectional"))
    )
    (net (code "89") (name "P3V3_MP2") (class "Default")
      (node (ref "C220") (pin "2") (pinfunction "2_2") (pintype "passive"))
      (node (ref "C307") (pin "2") (pinfunction "2_2") (pintype "passive"))
      (node (ref "IC45") (pin "4") (pinfunction "VCC_4") (pintype "power_in"))
      (node (ref "IC46") (pin "8") (pinfunction "VCC_8") (pintype "power_in"))
      (node (ref "J9") (pin "30") (pinfunction "30_30") (pintype "bidirectional"))
    )
    (net (code "90") (name "P12V0_DIOT") (class "Default")
      (node (ref "R257") (pin "1") (pinfunction "1_1") (pintype "passive"))
      (node (ref "R260") (pin "1") (pinfunction "1_1") (pintype "passive"))
      (node (ref "R261") (pin "1") (pinfunction "1_1") (pintype "passive"))
      (node (ref "R262") (pin "1") (pinfunction "1_1") (pintype "passive"))
    )
    (net (code "91") (name "P12V0_EEM") (class "Default")
      (node (ref "J8") (pin "28") (pinfunction "28_28") (pintype "bidirectional"))
      (node (ref "J8") (pin "29") (pinfunction "29_29") (pintype "bidirectional"))
      (node (ref "J9") (pin "28") (pinfunction "28_28") (pintype "bidirectional"))
      (node (ref "J9") (pin "29") (pinfunction "29_29") (pintype "bidirectional"))
      (node (ref "R257") (pin "2") (pinfunction "2_2") (pintype "passive"))
      (node (ref "R260") (pin "2") (pinfunction "2_2") (pintype "passive"))
      (node (ref "R261") (pin "2") (pinfunction "2_2") (pintype "passive"))
      (node (ref "R262") (pin "2") (pinfunction "2_2") (pintype "passive"))
    )
    (net (code "92") (name "unconnected-(D23D-C-Pad5)") (class "Default")
      (node (ref "D23") (pin "5") (pinfunction "C_5") (pintype "passive+no_connect"))
    )
    (net (code "93") (name "unconnected-(IC43-NC-Pad5)") (class "Default")
      (node (ref "IC43") (pin "5") (pinfunction "NC_5") (pintype "passive+no_connect"))
    )
    (net (code "94") (name "unconnected-(IC44-NC-Pad7)") (class "Default")
      (node (ref "IC44") (pin "7") (pinfunction "NC_7") (pintype "passive+no_connect"))
    )
    (net (code "95") (name "unconnected-(IC45-NC-Pad5)") (class "Default")
      (node (ref "IC45") (pin "5") (pinfunction "NC_5") (pintype "passive+no_connect"))
    )
    (net (code "96") (name "unconnected-(IC46-NC-Pad7)") (class "Default")
      (node (ref "IC46") (pin "7") (pinfunction "NC_7") (pintype "passive+no_connect"))
    )
  )
)
